# audio.net
KiCad netlist of a schematic drawn in EAGLE
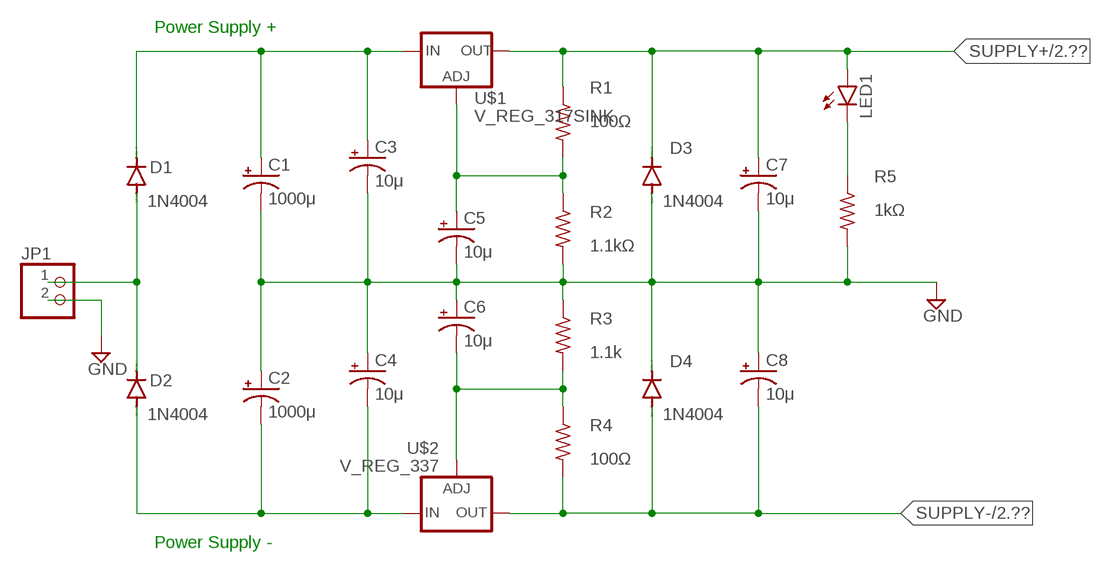
[diagram p0: schematic, sheet 1]
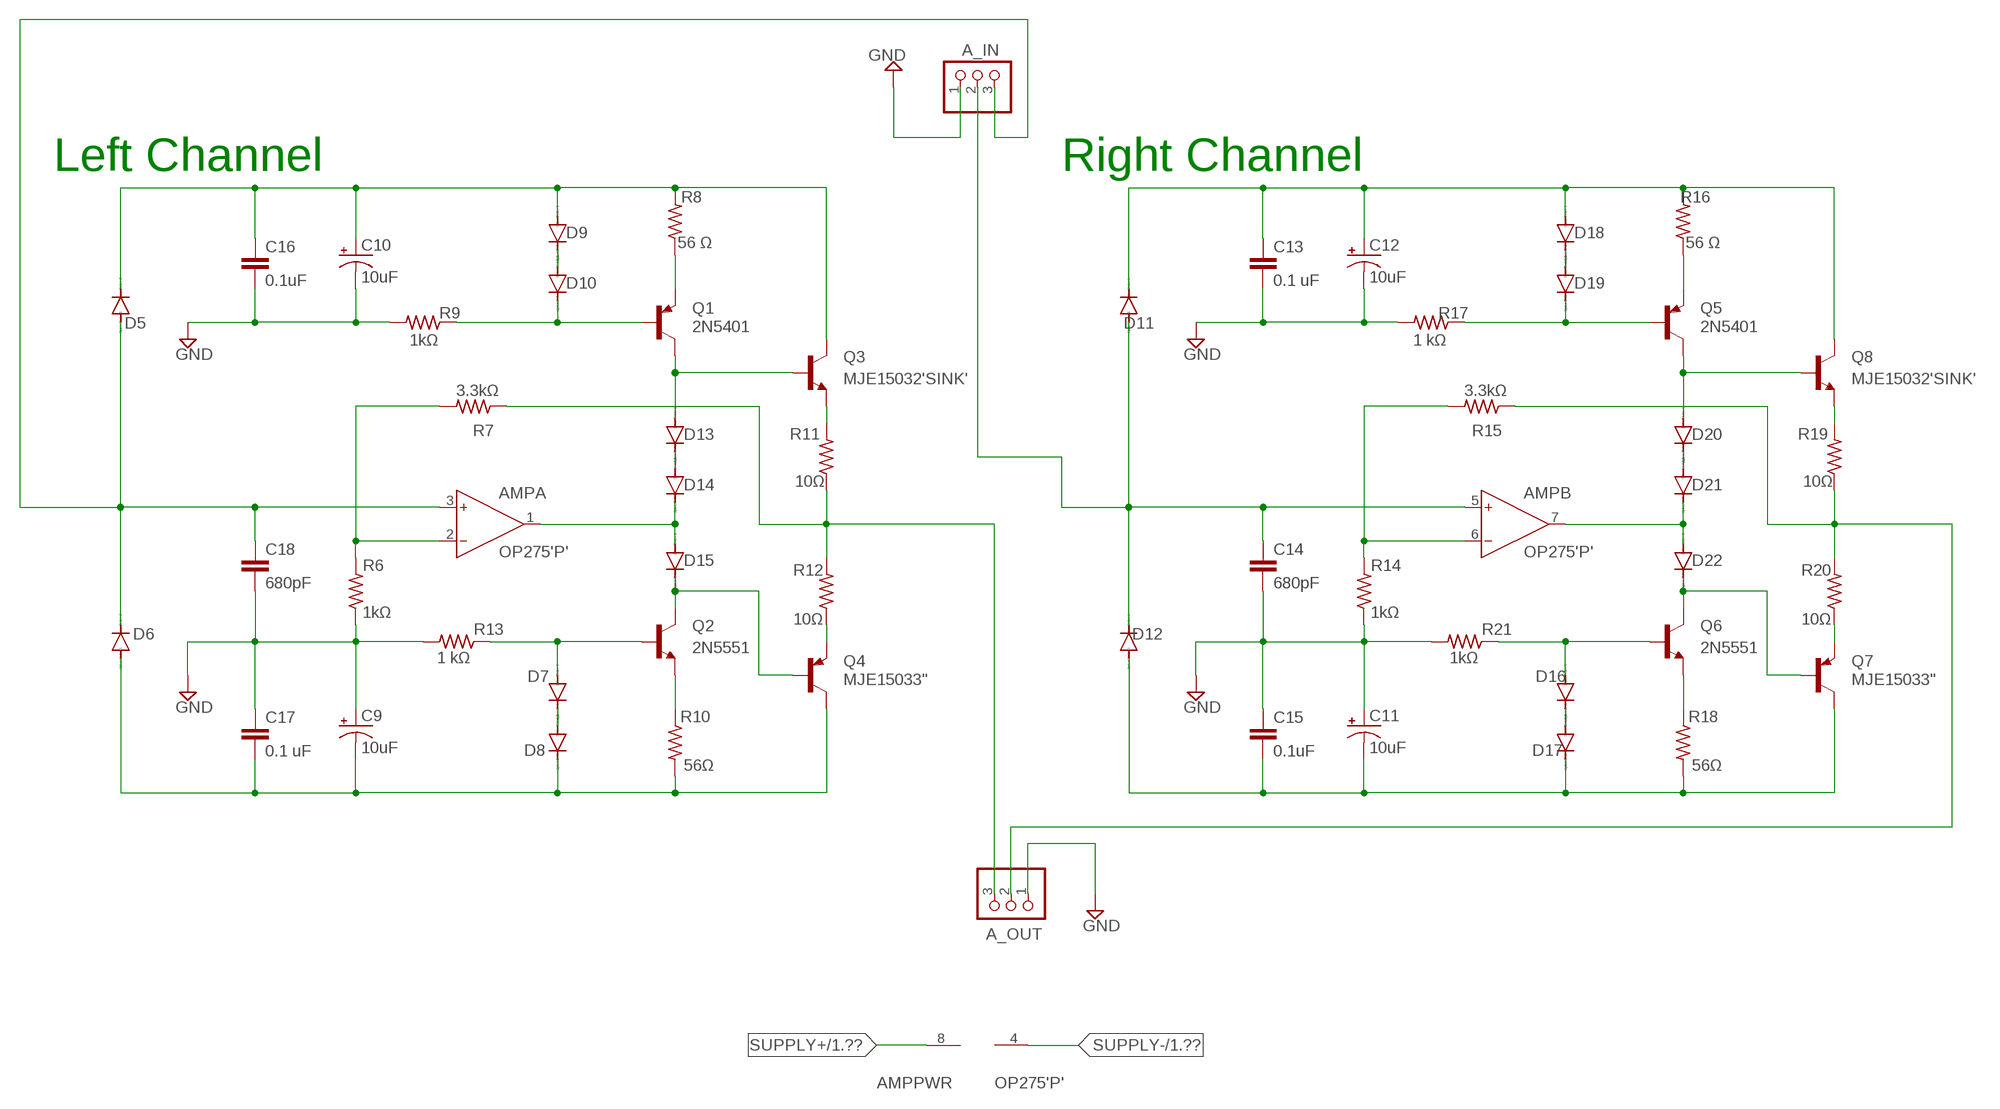
[diagram p1: schematic, sheet 2]

(export (version "E")
  (design (tool "Eeschema 10.0.6"))
  (components
    (comp (ref "AMP")
      (value "OP275'P'")
      (footprint "eagle-import:DIL08")
      (libsource (lib "eagle-import") (part "OP275'P'"))
    )
    (comp (ref "A_IN")
      (value "PINHD-1X3")
      (footprint "eagle-import:1X03")
      (libsource (lib "eagle-import") (part "PINHD-1X3"))
    )
    (comp (ref "A_OUT")
      (value "PINHD-1X3")
      (footprint "eagle-import:1X03")
      (libsource (lib "eagle-import") (part "PINHD-1X3"))
    )
    (comp (ref "C9")
      (value "10uF")
      (footprint "eagle-import:E1,8-4")
      (libsource (lib "eagle-import") (part "CPOL-USE1.8-4"))
    )
    (comp (ref "C10")
      (value "10uF")
      (footprint "eagle-import:E1,8-4")
      (libsource (lib "eagle-import") (part "CPOL-USE1.8-4"))
    )
    (comp (ref "C11")
      (value "10uF")
      (footprint "eagle-import:E1,8-4")
      (libsource (lib "eagle-import") (part "CPOL-USE1.8-4"))
    )
    (comp (ref "C12")
      (value "10uF")
      (footprint "eagle-import:E1,8-4")
      (libsource (lib "eagle-import") (part "CPOL-USE1.8-4"))
    )
    (comp (ref "C13")
      (value "0.1 uF")
      (footprint "eagle-import:C2.5-3")
      (libsource (lib "eagle-import") (part "C2,5-3"))
    )
    (comp (ref "C14")
      (value "680pF")
      (footprint "eagle-import:C2.5-3")
      (libsource (lib "eagle-import") (part "C2,5-3"))
    )
    (comp (ref "C15")
      (value "0.1uF")
      (footprint "eagle-import:C2.5-3")
      (libsource (lib "eagle-import") (part "C2,5-3"))
    )
    (comp (ref "C16")
      (value "0.1uF")
      (footprint "eagle-import:C2.5-3")
      (libsource (lib "eagle-import") (part "C2,5-3"))
    )
    (comp (ref "C17")
      (value "0.1 uF")
      (footprint "eagle-import:C2.5-3")
      (libsource (lib "eagle-import") (part "C2,5-3"))
    )
    (comp (ref "C18")
      (value "680pF")
      (footprint "eagle-import:C2.5-3")
      (libsource (lib "eagle-import") (part "C2,5-3"))
    )
    (comp (ref "D5")
      (value "1N4148DO35-7")
      (footprint "eagle-import:DO35-7")
      (libsource (lib "eagle-import") (part "1N4148DO35-7"))
    )
    (comp (ref "D6")
      (value "1N4148DO35-7")
      (footprint "eagle-import:DO35-7")
      (libsource (lib "eagle-import") (part "1N4148DO35-7"))
    )
    (comp (ref "D7")
      (value "1N4148DO35-7")
      (footprint "eagle-import:DO35-7")
      (libsource (lib "eagle-import") (part "1N4148DO35-7"))
    )
    (comp (ref "D8")
      (value "1N4148DO35-7")
      (footprint "eagle-import:DO35-7")
      (libsource (lib "eagle-import") (part "1N4148DO35-7"))
    )
    (comp (ref "D9")
      (value "1N4148DO35-7")
      (footprint "eagle-import:DO35-7")
      (libsource (lib "eagle-import") (part "1N4148DO35-7"))
    )
    (comp (ref "D10")
      (value "1N4148DO35-7")
      (footprint "eagle-import:DO35-7")
      (libsource (lib "eagle-import") (part "1N4148DO35-7"))
    )
    (comp (ref "D11")
      (value "1N4148DO35-7")
      (footprint "eagle-import:DO35-7")
      (libsource (lib "eagle-import") (part "1N4148DO35-7"))
    )
    (comp (ref "D12")
      (value "1N4148DO35-7")
      (footprint "eagle-import:DO35-7")
      (libsource (lib "eagle-import") (part "1N4148DO35-7"))
    )
    (comp (ref "D13")
      (value "1N4148DO35-7")
      (footprint "eagle-import:DO35-7")
      (libsource (lib "eagle-import") (part "1N4148DO35-7"))
    )
    (comp (ref "D14")
      (value "1N4148DO35-7")
      (footprint "eagle-import:DO35-7")
      (libsource (lib "eagle-import") (part "1N4148DO35-7"))
    )
    (comp (ref "D15")
      (value "1N4148DO35-7")
      (footprint "eagle-import:DO35-7")
      (libsource (lib "eagle-import") (part "1N4148DO35-7"))
    )
    (comp (ref "D16")
      (value "1N4148DO35-7")
      (footprint "eagle-import:DO35-7")
      (libsource (lib "eagle-import") (part "1N4148DO35-7"))
    )
    (comp (ref "D17")
      (value "1N4148DO35-7")
      (footprint "eagle-import:DO35-7")
      (libsource (lib "eagle-import") (part "1N4148DO35-7"))
    )
    (comp (ref "D18")
      (value "1N4148DO35-7")
      (footprint "eagle-import:DO35-7")
      (libsource (lib "eagle-import") (part "1N4148DO35-7"))
    )
    (comp (ref "D19")
      (value "1N4148DO35-7")
      (footprint "eagle-import:DO35-7")
      (libsource (lib "eagle-import") (part "1N4148DO35-7"))
    )
    (comp (ref "D20")
      (value "1N4148DO35-7")
      (footprint "eagle-import:DO35-7")
      (libsource (lib "eagle-import") (part "1N4148DO35-7"))
    )
    (comp (ref "D21")
      (value "1N4148DO35-7")
      (footprint "eagle-import:DO35-7")
      (libsource (lib "eagle-import") (part "1N4148DO35-7"))
    )
    (comp (ref "D22")
      (value "1N4148DO35-7")
      (footprint "eagle-import:DO35-7")
      (libsource (lib "eagle-import") (part "1N4148DO35-7"))
    )
    (comp (ref "Q1")
      (value "2N5401")
      (footprint "eagle-import:2N5401")
      (libsource (lib "eagle-import") (part "2N5401"))
    )
    (comp (ref "Q2")
      (value "2N5551")
      (footprint "eagle-import:2N5551")
      (libsource (lib "eagle-import") (part "2N5551"))
    )
    (comp (ref "Q3")
      (value "MJE15032'SINK'")
      (footprint "eagle-import:TO220V-SINK")
      (libsource (lib "eagle-import") (part "engr301_Library_MJE15032'SINK'"))
    )
    (comp (ref "Q4")
      (value "MJE15033\"")
      (footprint "eagle-import:TO220V-SINK")
      (libsource (lib "eagle-import") (part "MJE15033{dblquote}"))
    )
    (comp (ref "Q5")
      (value "2N5401")
      (footprint "eagle-import:2N5401")
      (libsource (lib "eagle-import") (part "2N5401"))
    )
    (comp (ref "Q6")
      (value "2N5551")
      (footprint "eagle-import:2N5551")
      (libsource (lib "eagle-import") (part "2N5551"))
    )
    (comp (ref "Q7")
      (value "MJE15033\"")
      (footprint "eagle-import:TO220V-SINK")
      (libsource (lib "eagle-import") (part "MJE15033{dblquote}"))
    )
    (comp (ref "Q8")
      (value "MJE15032'SINK'")
      (footprint "eagle-import:TO220V-SINK")
      (libsource (lib "eagle-import") (part "engr301_Library_MJE15032'SINK'"))
    )
    (comp (ref "R6")
      (value "1kΩ")
      (footprint "eagle-import:0204_7")
      (libsource (lib "eagle-import") (part "R-US_0204/7"))
    )
    (comp (ref "R7")
      (value "3.3kΩ")
      (footprint "eagle-import:0204_7")
      (libsource (lib "eagle-import") (part "R-US_0204/7"))
    )
    (comp (ref "R8")
      (value "56 Ω")
      (footprint "eagle-import:0204_7")
      (libsource (lib "eagle-import") (part "R-US_0204/7"))
    )
    (comp (ref "R9")
      (value "1kΩ")
      (footprint "eagle-import:0204_7")
      (libsource (lib "eagle-import") (part "R-US_0204/7"))
    )
    (comp (ref "R10")
      (value "56Ω")
      (footprint "eagle-import:0204_7")
      (libsource (lib "eagle-import") (part "R-US_0204/7"))
    )
    (comp (ref "R11")
      (value "10Ω")
      (footprint "eagle-import:0204_7")
      (libsource (lib "eagle-import") (part "R-US_0204/7"))
    )
    (comp (ref "R12")
      (value "10Ω")
      (footprint "eagle-import:0204_7")
      (libsource (lib "eagle-import") (part "R-US_0204/7"))
    )
    (comp (ref "R13")
      (value "1 kΩ")
      (footprint "eagle-import:0204_7")
      (libsource (lib "eagle-import") (part "R-US_0204/7"))
    )
    (comp (ref "R14")
      (value "1kΩ")
      (footprint "eagle-import:0204_7")
      (libsource (lib "eagle-import") (part "R-US_0204/7"))
    )
    (comp (ref "R15")
      (value "3.3kΩ")
      (footprint "eagle-import:0204_7")
      (libsource (lib "eagle-import") (part "R-US_0204/7"))
    )
    (comp (ref "R16")
      (value "56 Ω")
      (footprint "eagle-import:0204_7")
      (libsource (lib "eagle-import") (part "R-US_0204/7"))
    )
    (comp (ref "R17")
      (value "1 kΩ")
      (footprint "eagle-import:0204_7")
      (libsource (lib "eagle-import") (part "R-US_0204/7"))
    )
    (comp (ref "R18")
      (value "56Ω")
      (footprint "eagle-import:0204_7")
      (libsource (lib "eagle-import") (part "R-US_0204/7"))
    )
    (comp (ref "R19")
      (value "10Ω")
      (footprint "eagle-import:0204_7")
      (libsource (lib "eagle-import") (part "R-US_0204/7"))
    )
    (comp (ref "R20")
      (value "10Ω")
      (footprint "eagle-import:0204_7")
      (libsource (lib "eagle-import") (part "R-US_0204/7"))
    )
    (comp (ref "R21")
      (value "1kΩ")
      (footprint "eagle-import:0204_7")
      (libsource (lib "eagle-import") (part "R-US_0204/7"))
    )
    (comp (ref "C1")
      (value "1000μ")
      (footprint "eagle-import:E3,5-10")
      (libsource (lib "eagle-import") (part "CPOL-USE3.5-10"))
    )
    (comp (ref "C2")
      (value "1000μ")
      (footprint "eagle-import:E3,5-10")
      (libsource (lib "eagle-import") (part "CPOL-USE3.5-10"))
    )
    (comp (ref "C3")
      (value "10μ")
      (footprint "eagle-import:E1,8-4")
      (libsource (lib "eagle-import") (part "CPOL-USE1.8-4"))
    )
    (comp (ref "C4")
      (value "10μ")
      (footprint "eagle-import:E1,8-4")
      (libsource (lib "eagle-import") (part "CPOL-USE1.8-4"))
    )
    (comp (ref "C5")
      (value "10μ")
      (footprint "eagle-import:E1,8-4")
      (libsource (lib "eagle-import") (part "CPOL-USE1.8-4"))
    )
    (comp (ref "C6")
      (value "10μ")
      (footprint "eagle-import:E1,8-4")
      (libsource (lib "eagle-import") (part "CPOL-USE1.8-4"))
    )
    (comp (ref "C7")
      (value "10μ")
      (footprint "eagle-import:E1,8-4")
      (libsource (lib "eagle-import") (part "CPOL-USE1.8-4"))
    )
    (comp (ref "C8")
      (value "10μ")
      (footprint "eagle-import:E1,8-4")
      (libsource (lib "eagle-import") (part "CPOL-USE1.8-4"))
    )
    (comp (ref "D1")
      (value "1N4004")
      (footprint "eagle-import:DO41-10")
      (libsource (lib "eagle-import") (part "1N4004"))
    )
    (comp (ref "D2")
      (value "1N4004")
      (footprint "eagle-import:DO41-10")
      (libsource (lib "eagle-import") (part "1N4004"))
    )
    (comp (ref "D3")
      (value "1N4004")
      (footprint "eagle-import:DO41-10")
      (libsource (lib "eagle-import") (part "1N4004"))
    )
    (comp (ref "D4")
      (value "1N4004")
      (footprint "eagle-import:DO41-10")
      (libsource (lib "eagle-import") (part "1N4004"))
    )
    (comp (ref "JP1")
      (value "PINHD-1X2")
      (footprint "eagle-import:1X02")
      (libsource (lib "eagle-import") (part "PINHD-1X2"))
    )
    (comp (ref "LED1")
      (value "LED3MM")
      (footprint "eagle-import:LED3MM")
      (libsource (lib "eagle-import") (part "LED3MM"))
    )
    (comp (ref "R1")
      (value "100Ω")
      (footprint "eagle-import:0204_7")
      (libsource (lib "eagle-import") (part "R-US_0204/7"))
    )
    (comp (ref "R2")
      (value "1.1kΩ")
      (footprint "eagle-import:0204_7")
      (libsource (lib "eagle-import") (part "R-US_0204/7"))
    )
    (comp (ref "R3")
      (value "1.1k")
      (footprint "eagle-import:0204_7")
      (libsource (lib "eagle-import") (part "R-US_0204/7"))
    )
    (comp (ref "R4")
      (value "100Ω")
      (footprint "eagle-import:0204_7")
      (libsource (lib "eagle-import") (part "R-US_0204/7"))
    )
    (comp (ref "R5")
      (value "1kΩ")
      (footprint "eagle-import:0204_7")
      (libsource (lib "eagle-import") (part "R-US_0204/7"))
    )
    (comp (ref "U$1")
      (value "V_REG_317SINK")
      (footprint "eagle-import:TO220-ADJ")
      (libsource (lib "eagle-import") (part "V_REG_317SINK"))
    )
    (comp (ref "U$2")
      (value "V_REG_337")
      (footprint "eagle-import:TO220-ADJ-NEG")
      (libsource (lib "eagle-import") (part "V_REG_337"))
    )
  )
  (nets
    (net (code "1") (name "GND") (class "Default")
      (node (ref "A_IN") (pin "1") (pinfunction "1_1") (pintype "passive"))
      (node (ref "A_OUT") (pin "1") (pinfunction "1_1") (pintype "passive"))
      (node (ref "C1") (pin "-") (pinfunction "-_-") (pintype "passive"))
      (node (ref "C10") (pin "-") (pinfunction "-_-") (pintype "passive"))
      (node (ref "C11") (pin "+") (pinfunction "+_+") (pintype "passive"))
      (node (ref "C12") (pin "-") (pinfunction "-_-") (pintype "passive"))
      (node (ref "C13") (pin "2") (pinfunction "2_2") (pintype "passive"))
      (node (ref "C14") (pin "2") (pinfunction "2_2") (pintype "passive"))
      (node (ref "C15") (pin "1") (pinfunction "1_1") (pintype "passive"))
      (node (ref "C16") (pin "2") (pinfunction "2_2") (pintype "passive"))
      (node (ref "C17") (pin "1") (pinfunction "1_1") (pintype "passive"))
      (node (ref "C18") (pin "2") (pinfunction "2_2") (pintype "passive"))
      (node (ref "C2") (pin "+") (pinfunction "+_+") (pintype "passive"))
      (node (ref "C3") (pin "-") (pinfunction "-_-") (pintype "passive"))
      (node (ref "C4") (pin "+") (pinfunction "+_+") (pintype "passive"))
      (node (ref "C5") (pin "-") (pinfunction "-_-") (pintype "passive"))
      (node (ref "C6") (pin "+") (pinfunction "+_+") (pintype "passive"))
      (node (ref "C7") (pin "-") (pinfunction "-_-") (pintype "passive"))
      (node (ref "C8") (pin "+") (pinfunction "+_+") (pintype "passive"))
      (node (ref "C9") (pin "+") (pinfunction "+_+") (pintype "passive"))
      (node (ref "D3") (pin "A") (pinfunction "A_A") (pintype "passive"))
      (node (ref "D4") (pin "C") (pinfunction "C_C") (pintype "passive"))
      (node (ref "JP1") (pin "2") (pinfunction "2_2") (pintype "passive"))
      (node (ref "R13") (pin "2") (pinfunction "2_2") (pintype "passive"))
      (node (ref "R14") (pin "1") (pinfunction "1_1") (pintype "passive"))
      (node (ref "R17") (pin "2") (pinfunction "2_2") (pintype "passive"))
      (node (ref "R2") (pin "2") (pinfunction "2_2") (pintype "passive"))
      (node (ref "R21") (pin "2") (pinfunction "2_2") (pintype "passive"))
      (node (ref "R3") (pin "1") (pinfunction "1_1") (pintype "passive"))
      (node (ref "R5") (pin "2") (pinfunction "2_2") (pintype "passive"))
      (node (ref "R6") (pin "1") (pinfunction "1_1") (pintype "passive"))
      (node (ref "R9") (pin "2") (pinfunction "2_2") (pintype "passive"))
    )
    (net (code "2") (name "Net-(AMPA-IN+)") (class "Default")
      (node (ref "AMP") (pin "3") (pinfunction "IN+_3") (pintype "input"))
      (node (ref "A_IN") (pin "3") (pinfunction "3_3") (pintype "passive"))
      (node (ref "C18") (pin "1") (pinfunction "1_1") (pintype "passive"))
      (node (ref "D5") (pin "A") (pinfunction "A_A") (pintype "passive"))
      (node (ref "D6") (pin "C") (pinfunction "C_C") (pintype "passive"))
    )
    (net (code "3") (name "Net-(AMPA-IN-)") (class "Default")
      (node (ref "AMP") (pin "2") (pinfunction "IN-_2") (pintype "input"))
      (node (ref "R6") (pin "2") (pinfunction "2_2") (pintype "passive"))
      (node (ref "R7") (pin "2") (pinfunction "2_2") (pintype "passive"))
    )
    (net (code "4") (name "Net-(AMPA-OUT)") (class "Default")
      (node (ref "AMP") (pin "1") (pinfunction "OUT_1") (pintype "output"))
      (node (ref "D14") (pin "C") (pinfunction "C_C") (pintype "passive"))
      (node (ref "D15") (pin "A") (pinfunction "A_A") (pintype "passive"))
    )
    (net (code "5") (name "Net-(AMPB-IN+)") (class "Default")
      (node (ref "AMP") (pin "5") (pinfunction "IN+_5") (pintype "input"))
      (node (ref "A_IN") (pin "2") (pinfunction "2_2") (pintype "passive"))
      (node (ref "C14") (pin "1") (pinfunction "1_1") (pintype "passive"))
      (node (ref "D11") (pin "A") (pinfunction "A_A") (pintype "passive"))
      (node (ref "D12") (pin "C") (pinfunction "C_C") (pintype "passive"))
    )
    (net (code "6") (name "Net-(AMPB-IN-)") (class "Default")
      (node (ref "AMP") (pin "6") (pinfunction "IN-_6") (pintype "input"))
      (node (ref "R14") (pin "2") (pinfunction "2_2") (pintype "passive"))
      (node (ref "R15") (pin "2") (pinfunction "2_2") (pintype "passive"))
    )
    (net (code "7") (name "Net-(AMPB-OUT)") (class "Default")
      (node (ref "AMP") (pin "7") (pinfunction "OUT_7") (pintype "output"))
      (node (ref "D21") (pin "C") (pinfunction "C_C") (pintype "passive"))
      (node (ref "D22") (pin "A") (pinfunction "A_A") (pintype "passive"))
    )
    (net (code "8") (name "Net-(A_OUT-Pad2)") (class "Default")
      (node (ref "A_OUT") (pin "2") (pinfunction "2_2") (pintype "passive"))
      (node (ref "R15") (pin "1") (pinfunction "1_1") (pintype "passive"))
      (node (ref "R19") (pin "1") (pinfunction "1_1") (pintype "passive"))
      (node (ref "R20") (pin "2") (pinfunction "2_2") (pintype "passive"))
    )
    (net (code "9") (name "Net-(A_OUT-Pad3)") (class "Default")
      (node (ref "A_OUT") (pin "3") (pinfunction "3_3") (pintype "passive"))
      (node (ref "R11") (pin "1") (pinfunction "1_1") (pintype "passive"))
      (node (ref "R12") (pin "2") (pinfunction "2_2") (pintype "passive"))
      (node (ref "R7") (pin "1") (pinfunction "1_1") (pintype "passive"))
    )
    (net (code "10") (name "Net-(C1-Pad+)") (class "Default")
      (node (ref "C1") (pin "+") (pinfunction "+_+") (pintype "passive"))
      (node (ref "C3") (pin "+") (pinfunction "+_+") (pintype "passive"))
      (node (ref "D1") (pin "C") (pinfunction "C_C") (pintype "passive"))
      (node (ref "U$1") (pin "IN") (pinfunction "IN_IN") (pintype "input"))
    )
    (net (code "11") (name "Net-(C2-Pad-)") (class "Default")
      (node (ref "C2") (pin "-") (pinfunction "-_-") (pintype "passive"))
      (node (ref "C4") (pin "-") (pinfunction "-_-") (pintype "passive"))
      (node (ref "D2") (pin "A") (pinfunction "A_A") (pintype "passive"))
      (node (ref "U$2") (pin "IN") (pinfunction "IN_IN") (pintype "input"))
    )
    (net (code "12") (name "Net-(C5-Pad+)") (class "Default")
      (node (ref "C5") (pin "+") (pinfunction "+_+") (pintype "passive"))
      (node (ref "R1") (pin "2") (pinfunction "2_2") (pintype "passive"))
      (node (ref "R2") (pin "1") (pinfunction "1_1") (pintype "passive"))
      (node (ref "U$1") (pin "ADJ") (pinfunction "ADJ_ADJ") (pintype "input"))
    )
    (net (code "13") (name "Net-(C6-Pad-)") (class "Default")
      (node (ref "C6") (pin "-") (pinfunction "-_-") (pintype "passive"))
      (node (ref "R3") (pin "2") (pinfunction "2_2") (pintype "passive"))
      (node (ref "R4") (pin "1") (pinfunction "1_1") (pintype "passive"))
      (node (ref "U$2") (pin "ADJ") (pinfunction "ADJ_ADJ") (pintype "input"))
    )
    (net (code "14") (name "Net-(D1-PadA)") (class "Default")
      (node (ref "D1") (pin "A") (pinfunction "A_A") (pintype "passive"))
      (node (ref "D2") (pin "C") (pinfunction "C_C") (pintype "passive"))
      (node (ref "JP1") (pin "1") (pinfunction "1_1") (pintype "passive"))
    )
    (net (code "15") (name "Net-(D7-PadA)") (class "Default")
      (node (ref "D7") (pin "A") (pinfunction "A_A") (pintype "passive"))
      (node (ref "Q2") (pin "B") (pinfunction "B_B") (pintype "passive"))
      (node (ref "R13") (pin "1") (pinfunction "1_1") (pintype "passive"))
    )
    (net (code "16") (name "Net-(D7-PadC)") (class "Default")
      (node (ref "D7") (pin "C") (pinfunction "C_C") (pintype "passive"))
      (node (ref "D8") (pin "A") (pinfunction "A_A") (pintype "passive"))
    )
    (net (code "17") (name "Net-(D10-PadA)") (class "Default")
      (node (ref "D10") (pin "A") (pinfunction "A_A") (pintype "passive"))
      (node (ref "D9") (pin "C") (pinfunction "C_C") (pintype "passive"))
    )
    (net (code "18") (name "Net-(D10-PadC)") (class "Default")
      (node (ref "D10") (pin "C") (pinfunction "C_C") (pintype "passive"))
      (node (ref "Q1") (pin "B") (pinfunction "B_B") (pintype "passive"))
      (node (ref "R9") (pin "1") (pinfunction "1_1") (pintype "passive"))
    )
    (net (code "19") (name "Net-(D13-PadC)") (class "Default")
      (node (ref "D13") (pin "C") (pinfunction "C_C") (pintype "passive"))
      (node (ref "D14") (pin "A") (pinfunction "A_A") (pintype "passive"))
    )
    (net (code "20") (name "Net-(D16-PadA)") (class "Default")
      (node (ref "D16") (pin "A") (pinfunction "A_A") (pintype "passive"))
      (node (ref "Q6") (pin "B") (pinfunction "B_B") (pintype "passive"))
      (node (ref "R21") (pin "1") (pinfunction "1_1") (pintype "passive"))
    )
    (net (code "21") (name "Net-(D16-PadC)") (class "Default")
      (node (ref "D16") (pin "C") (pinfunction "C_C") (pintype "passive"))
      (node (ref "D17") (pin "A") (pinfunction "A_A") (pintype "passive"))
    )
    (net (code "22") (name "Net-(D18-PadC)") (class "Default")
      (node (ref "D18") (pin "C") (pinfunction "C_C") (pintype "passive"))
      (node (ref "D19") (pin "A") (pinfunction "A_A") (pintype "passive"))
    )
    (net (code "23") (name "Net-(D19-PadC)") (class "Default")
      (node (ref "D19") (pin "C") (pinfunction "C_C") (pintype "passive"))
      (node (ref "Q5") (pin "B") (pinfunction "B_B") (pintype "passive"))
      (node (ref "R17") (pin "1") (pinfunction "1_1") (pintype "passive"))
    )
    (net (code "24") (name "Net-(D20-PadC)") (class "Default")
      (node (ref "D20") (pin "C") (pinfunction "C_C") (pintype "passive"))
      (node (ref "D21") (pin "A") (pinfunction "A_A") (pintype "passive"))
    )
    (net (code "25") (name "Net-(LED1-C)") (class "Default")
      (node (ref "LED1") (pin "K") (pinfunction "C_K") (pintype "passive"))
      (node (ref "R5") (pin "1") (pinfunction "1_1") (pintype "passive"))
    )
    (net (code "26") (name "Net-(Q1-PadE)") (class "Default")
      (node (ref "Q1") (pin "E") (pinfunction "E_E") (pintype "passive"))
      (node (ref "R8") (pin "1") (pinfunction "1_1") (pintype "passive"))
    )
    (net (code "27") (name "Net-(Q2-PadE)") (class "Default")
      (node (ref "Q2") (pin "E") (pinfunction "E_E") (pintype "passive"))
      (node (ref "R10") (pin "1") (pinfunction "1_1") (pintype "passive"))
    )
    (net (code "28") (name "Net-(Q3-B)") (class "Default")
      (node (ref "D13") (pin "A") (pinfunction "A_A") (pintype "passive"))
      (node (ref "Q1") (pin "C") (pinfunction "C_C") (pintype "passive"))
      (node (ref "Q3") (pin "1") (pinfunction "B_1") (pintype "passive"))
    )
    (net (code "29") (name "Net-(Q3-C)") (class "Default")
      (node (ref "C10") (pin "+") (pinfunction "+_+") (pintype "passive"))
      (node (ref "C16") (pin "1") (pinfunction "1_1") (pintype "passive"))
      (node (ref "D5") (pin "C") (pinfunction "C_C") (pintype "passive"))
      (node (ref "D9") (pin "A") (pinfunction "A_A") (pintype "passive"))
      (node (ref "Q3") (pin "2") (pinfunction "C_2") (pintype "passive"))
      (node (ref "R8") (pin "2") (pinfunction "2_2") (pintype "passive"))
    )
    (net (code "30") (name "Net-(Q3-E)") (class "Default")
      (node (ref "Q3") (pin "3") (pinfunction "E_3") (pintype "passive"))
      (node (ref "R11") (pin "2") (pinfunction "2_2") (pintype "passive"))
    )
    (net (code "31") (name "Net-(Q4-B)") (class "Default")
      (node (ref "D15") (pin "C") (pinfunction "C_C") (pintype "passive"))
      (node (ref "Q2") (pin "C") (pinfunction "C_C") (pintype "passive"))
      (node (ref "Q4") (pin "1") (pinfunction "B_1") (pintype "passive"))
    )
    (net (code "32") (name "Net-(Q4-C)") (class "Default")
      (node (ref "C17") (pin "2") (pinfunction "2_2") (pintype "passive"))
      (node (ref "C9") (pin "-") (pinfunction "-_-") (pintype "passive"))
      (node (ref "D6") (pin "A") (pinfunction "A_A") (pintype "passive"))
      (node (ref "D8") (pin "C") (pinfunction "C_C") (pintype "passive"))
      (node (ref "Q4") (pin "2") (pinfunction "C_2") (pintype "passive"))
      (node (ref "R10") (pin "2") (pinfunction "2_2") (pintype "passive"))
    )
    (net (code "33") (name "Net-(Q4-E)") (class "Default")
      (node (ref "Q4") (pin "3") (pinfunction "E_3") (pintype "passive"))
      (node (ref "R12") (pin "1") (pinfunction "1_1") (pintype "passive"))
    )
    (net (code "34") (name "Net-(Q5-PadE)") (class "Default")
      (node (ref "Q5") (pin "E") (pinfunction "E_E") (pintype "passive"))
      (node (ref "R16") (pin "1") (pinfunction "1_1") (pintype "passive"))
    )
    (net (code "35") (name "Net-(Q6-PadE)") (class "Default")
      (node (ref "Q6") (pin "E") (pinfunction "E_E") (pintype "passive"))
      (node (ref "R18") (pin "1") (pinfunction "1_1") (pintype "passive"))
    )
    (net (code "36") (name "Net-(Q7-B)") (class "Default")
      (node (ref "D22") (pin "C") (pinfunction "C_C") (pintype "passive"))
      (node (ref "Q6") (pin "C") (pinfunction "C_C") (pintype "passive"))
      (node (ref "Q7") (pin "1") (pinfunction "B_1") (pintype "passive"))
    )
    (net (code "37") (name "Net-(Q7-C)") (class "Default")
      (node (ref "C11") (pin "-") (pinfunction "-_-") (pintype "passive"))
      (node (ref "C15") (pin "2") (pinfunction "2_2") (pintype "passive"))
      (node (ref "D12") (pin "A") (pinfunction "A_A") (pintype "passive"))
      (node (ref "D17") (pin "C") (pinfunction "C_C") (pintype "passive"))
      (node (ref "Q7") (pin "2") (pinfunction "C_2") (pintype "passive"))
      (node (ref "R18") (pin "2") (pinfunction "2_2") (pintype "passive"))
    )
    (net (code "38") (name "Net-(Q7-E)") (class "Default")
      (node (ref "Q7") (pin "3") (pinfunction "E_3") (pintype "passive"))
      (node (ref "R20") (pin "1") (pinfunction "1_1") (pintype "passive"))
    )
    (net (code "39") (name "Net-(Q8-B)") (class "Default")
      (node (ref "D20") (pin "A") (pinfunction "A_A") (pintype "passive"))
      (node (ref "Q5") (pin "C") (pinfunction "C_C") (pintype "passive"))
      (node (ref "Q8") (pin "1") (pinfunction "B_1") (pintype "passive"))
    )
    (net (code "40") (name "Net-(Q8-C)") (class "Default")
      (node (ref "C12") (pin "+") (pinfunction "+_+") (pintype "passive"))
      (node (ref "C13") (pin "1") (pinfunction "1_1") (pintype "passive"))
      (node (ref "D11") (pin "C") (pinfunction "C_C") (pintype "passive"))
      (node (ref "D18") (pin "A") (pinfunction "A_A") (pintype "passive"))
      (node (ref "Q8") (pin "2") (pinfunction "C_2") (pintype "passive"))
      (node (ref "R16") (pin "2") (pinfunction "2_2") (pintype "passive"))
    )
    (net (code "41") (name "Net-(Q8-E)") (class "Default")
      (node (ref "Q8") (pin "3") (pinfunction "E_3") (pintype "passive"))
      (node (ref "R19") (pin "2") (pinfunction "2_2") (pintype "passive"))
    )
    (net (code "42") (name "SUPPLY+") (class "Default")
      (node (ref "AMP") (pin "8") (pinfunction "V+_8") (pintype "power_in"))
      (node (ref "C7") (pin "+") (pinfunction "+_+") (pintype "passive"))
      (node (ref "D3") (pin "C") (pinfunction "C_C") (pintype "passive"))
      (node (ref "LED1") (pin "A") (pinfunction "A_A") (pintype "passive"))
      (node (ref "R1") (pin "1") (pinfunction "1_1") (pintype "passive"))
      (node (ref "U$1") (pin "OUT") (pinfunction "OUT_OUT") (pintype "output"))
    )
    (net (code "43") (name "SUPPLY-") (class "Default")
      (node (ref "AMP") (pin "4") (pinfunction "V-_4") (pintype "power_in"))
      (node (ref "C8") (pin "-") (pinfunction "-_-") (pintype "passive"))
      (node (ref "D4") (pin "A") (pinfunction "A_A") (pintype "passive"))
      (node (ref "R4") (pin "2") (pinfunction "2_2") (pintype "passive"))
      (node (ref "U$2") (pin "OUT") (pinfunction "OUT_OUT") (pintype "output"))
    )
  )
)
